# ExternalLEDs.net
KiCad netlist of a schematic drawn in EAGLE
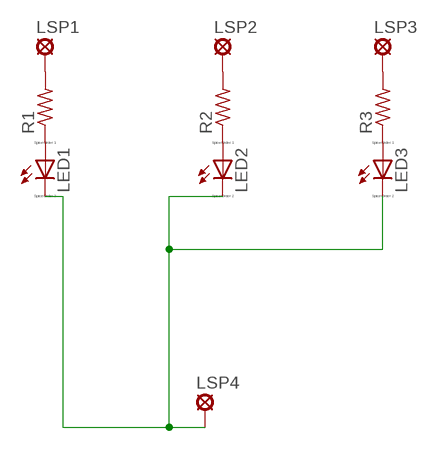
[diagram p0: schematic, sheet 1]

(export (version "E")
  (design (tool "Eeschema 10.0.6"))
  (components
    (comp (ref "LED1")
      (value "LED_E")
      (footprint "eagle-import:LED_1206")
      (libsource (lib "eagle-import") (part "LED_E"))
    )
    (comp (ref "LED2")
      (value "LED_E")
      (footprint "eagle-import:LED_1206")
      (libsource (lib "eagle-import") (part "LED_E"))
    )
    (comp (ref "LED3")
      (value "LED_E")
      (footprint "eagle-import:LED_1206")
      (libsource (lib "eagle-import") (part "LED_E"))
    )
    (comp (ref "LSP1")
      (value "LSP11")
      (footprint "eagle-import:LSP11")
      (libsource (lib "eagle-import") (part "LSP11"))
    )
    (comp (ref "LSP2")
      (value "LSP11")
      (footprint "eagle-import:LSP11")
      (libsource (lib "eagle-import") (part "LSP11"))
    )
    (comp (ref "LSP3")
      (value "LSP11")
      (footprint "eagle-import:LSP11")
      (libsource (lib "eagle-import") (part "LSP11"))
    )
    (comp (ref "LSP4")
      (value "LSP11")
      (footprint "eagle-import:LSP11")
      (libsource (lib "eagle-import") (part "LSP11"))
    )
    (comp (ref "R1")
      (value "R-US_0204/7")
      (footprint "eagle-import:0204_7")
      (libsource (lib "eagle-import") (part "R-US_0204/7"))
    )
    (comp (ref "R2")
      (value "R-US_0204/7")
      (footprint "eagle-import:0204_7")
      (libsource (lib "eagle-import") (part "R-US_0204/7"))
    )
    (comp (ref "R3")
      (value "R-US_0204/7")
      (footprint "eagle-import:0204_7")
      (libsource (lib "eagle-import") (part "R-US_0204/7"))
    )
  )
  (nets
    (net (code "1") (name "Net-(LED1-PadA)") (class "Default")
      (node (ref "LED1") (pin "A") (pinfunction "A_A") (pintype "passive"))
      (node (ref "R1") (pin "1") (pinfunction "1_1") (pintype "passive"))
    )
    (net (code "2") (name "Net-(LED1-PadC)") (class "Default")
      (node (ref "LED1") (pin "C") (pinfunction "C_C") (pintype "passive"))
      (node (ref "LED2") (pin "C") (pinfunction "C_C") (pintype "passive"))
      (node (ref "LED3") (pin "C") (pinfunction "C_C") (pintype "passive"))
      (node (ref "LSP4") (pin "MP") (pinfunction "MP_MP") (pintype "passive"))
    )
    (net (code "3") (name "Net-(LED2-PadA)") (class "Default")
      (node (ref "LED2") (pin "A") (pinfunction "A_A") (pintype "passive"))
      (node (ref "R2") (pin "1") (pinfunction "1_1") (pintype "passive"))
    )
    (net (code "4") (name "Net-(LED3-PadA)") (class "Default")
      (node (ref "LED3") (pin "A") (pinfunction "A_A") (pintype "passive"))
      (node (ref "R3") (pin "1") (pinfunction "1_1") (pintype "passive"))
    )
    (net (code "5") (name "Net-(LSP1-PadMP)") (class "Default")
      (node (ref "LSP1") (pin "MP") (pinfunction "MP_MP") (pintype "passive"))
      (node (ref "R1") (pin "2") (pinfunction "2_2") (pintype "passive"))
    )
    (net (code "6") (name "Net-(LSP2-PadMP)") (class "Default")
      (node (ref "LSP2") (pin "MP") (pinfunction "MP_MP") (pintype "passive"))
      (node (ref "R2") (pin "2") (pinfunction "2_2") (pintype "passive"))
    )
    (net (code "7") (name "Net-(LSP3-PadMP)") (class "Default")
      (node (ref "LSP3") (pin "MP") (pinfunction "MP_MP") (pintype "passive"))
      (node (ref "R3") (pin "2") (pinfunction "2_2") (pintype "passive"))
    )
  )
)
